# led_board_v2.net
KiCad netlist of a schematic drawn in EAGLE
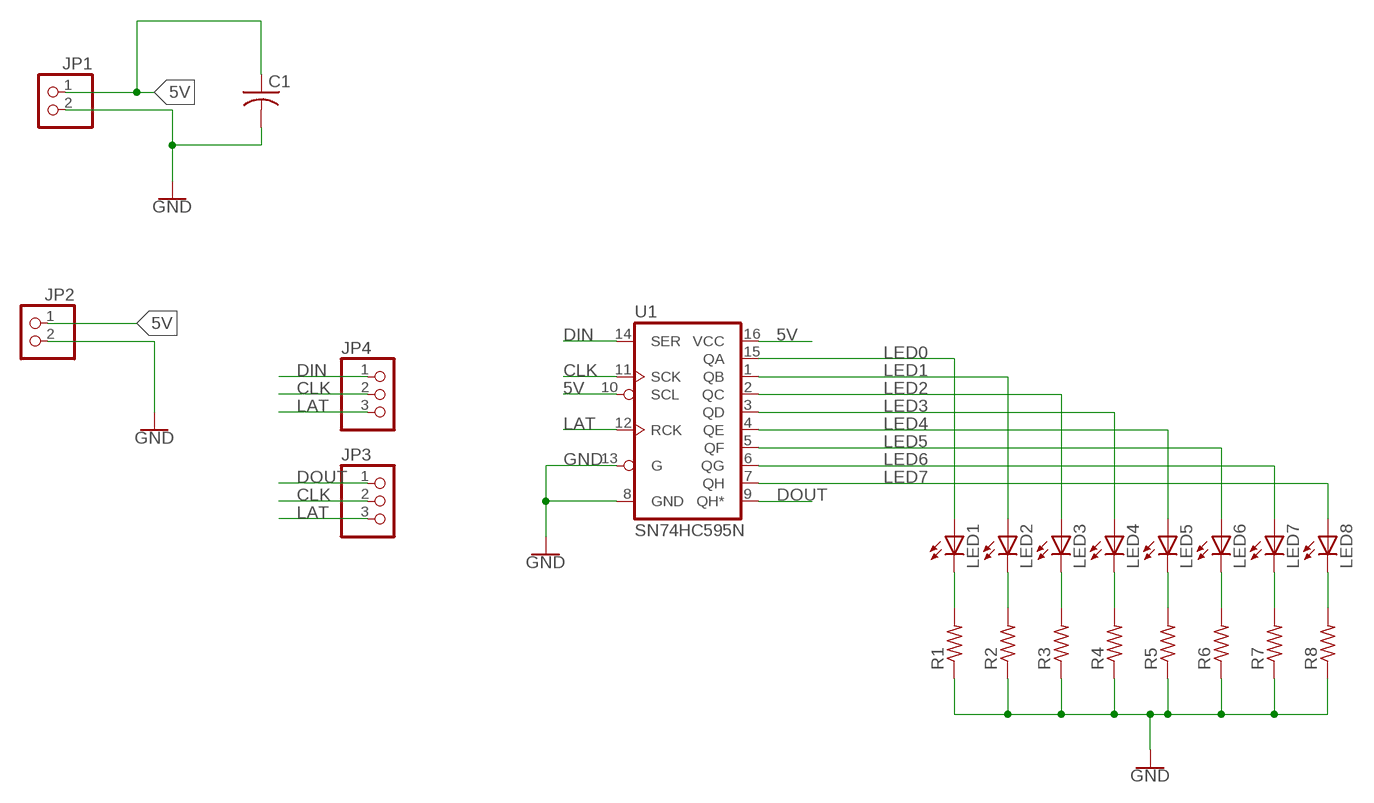
[diagram p0: schematic, sheet 1]

(export (version "E")
  (design (tool "Eeschema 10.0.6"))
  (components
    (comp (ref "C1")
      (value "C-US025-030X050")
      (footprint "eagle-import:C025-030X050")
      (libsource (lib "eagle-import") (part "C-US025-030X050"))
    )
    (comp (ref "JP1")
      (value "PINHD-1X2")
      (footprint "eagle-import:1X02")
      (libsource (lib "eagle-import") (part "PINHD-1X2"))
    )
    (comp (ref "JP2")
      (value "PINHD-1X2")
      (footprint "eagle-import:1X02")
      (libsource (lib "eagle-import") (part "PINHD-1X2"))
    )
    (comp (ref "JP3")
      (value "PINHD-1X3")
      (footprint "eagle-import:1X03")
      (libsource (lib "eagle-import") (part "PINHD-1X3"))
    )
    (comp (ref "JP4")
      (value "PINHD-1X3")
      (footprint "eagle-import:1X03")
      (libsource (lib "eagle-import") (part "PINHD-1X3"))
    )
    (comp (ref "LED1")
      (value "LED3MM")
      (footprint "eagle-import:LED3MM")
      (libsource (lib "eagle-import") (part "LED3MM"))
    )
    (comp (ref "LED2")
      (value "LED3MM")
      (footprint "eagle-import:LED3MM")
      (libsource (lib "eagle-import") (part "LED3MM"))
    )
    (comp (ref "LED3")
      (value "LED3MM")
      (footprint "eagle-import:LED3MM")
      (libsource (lib "eagle-import") (part "LED3MM"))
    )
    (comp (ref "LED4")
      (value "LED3MM")
      (footprint "eagle-import:LED3MM")
      (libsource (lib "eagle-import") (part "LED3MM"))
    )
    (comp (ref "LED5")
      (value "LED3MM")
      (footprint "eagle-import:LED3MM")
      (libsource (lib "eagle-import") (part "LED3MM"))
    )
    (comp (ref "LED6")
      (value "LED3MM")
      (footprint "eagle-import:LED3MM")
      (libsource (lib "eagle-import") (part "LED3MM"))
    )
    (comp (ref "LED7")
      (value "LED3MM")
      (footprint "eagle-import:LED3MM")
      (libsource (lib "eagle-import") (part "LED3MM"))
    )
    (comp (ref "LED8")
      (value "LED3MM")
      (footprint "eagle-import:LED3MM")
      (libsource (lib "eagle-import") (part "LED3MM"))
    )
    (comp (ref "R1")
      (value "R-US_0207/7")
      (footprint "eagle-import:0207_7")
      (libsource (lib "eagle-import") (part "R-US_0207/7"))
    )
    (comp (ref "R2")
      (value "R-US_0207/7")
      (footprint "eagle-import:0207_7")
      (libsource (lib "eagle-import") (part "R-US_0207/7"))
    )
    (comp (ref "R3")
      (value "R-US_0207/7")
      (footprint "eagle-import:0207_7")
      (libsource (lib "eagle-import") (part "R-US_0207/7"))
    )
    (comp (ref "R4")
      (value "R-US_0207/7")
      (footprint "eagle-import:0207_7")
      (libsource (lib "eagle-import") (part "R-US_0207/7"))
    )
    (comp (ref "R5")
      (value "R-US_0207/7")
      (footprint "eagle-import:0207_7")
      (libsource (lib "eagle-import") (part "R-US_0207/7"))
    )
    (comp (ref "R6")
      (value "R-US_0207/7")
      (footprint "eagle-import:0207_7")
      (libsource (lib "eagle-import") (part "R-US_0207/7"))
    )
    (comp (ref "R7")
      (value "R-US_0207/7")
      (footprint "eagle-import:0207_7")
      (libsource (lib "eagle-import") (part "R-US_0207/7"))
    )
    (comp (ref "R8")
      (value "R-US_0207/7")
      (footprint "eagle-import:0207_7")
      (libsource (lib "eagle-import") (part "R-US_0207/7"))
    )
    (comp (ref "U1")
      (value "SN74HC595N")
      (footprint "eagle-import:DIP16")
      (libsource (lib "eagle-import") (part "74595NHC"))
    )
  )
  (nets
    (net (code "1") (name "/CLK") (class "Default")
      (node (ref "JP3") (pin "2") (pinfunction "2_2") (pintype "passive"))
      (node (ref "JP4") (pin "2") (pinfunction "2_2") (pintype "passive"))
      (node (ref "U1") (pin "11") (pinfunction "SCK_11") (pintype "input"))
    )
    (net (code "2") (name "/DIN") (class "Default")
      (node (ref "JP4") (pin "1") (pinfunction "1_1") (pintype "passive"))
      (node (ref "U1") (pin "14") (pinfunction "SER_14") (pintype "input"))
    )
    (net (code "3") (name "/DOUT") (class "Default")
      (node (ref "JP3") (pin "1") (pinfunction "1_1") (pintype "passive"))
      (node (ref "U1") (pin "9") (pinfunction "QH*_9") (pintype "tri_state"))
    )
    (net (code "4") (name "/LAT") (class "Default")
      (node (ref "JP3") (pin "3") (pinfunction "3_3") (pintype "passive"))
      (node (ref "JP4") (pin "3") (pinfunction "3_3") (pintype "passive"))
      (node (ref "U1") (pin "12") (pinfunction "RCK_12") (pintype "input"))
    )
    (net (code "5") (name "/LED0") (class "Default")
      (node (ref "LED1") (pin "A") (pinfunction "A_A") (pintype "passive"))
      (node (ref "U1") (pin "15") (pinfunction "QA_15") (pintype "tri_state"))
    )
    (net (code "6") (name "/LED1") (class "Default")
      (node (ref "LED2") (pin "A") (pinfunction "A_A") (pintype "passive"))
      (node (ref "U1") (pin "1") (pinfunction "QB_1") (pintype "tri_state"))
    )
    (net (code "7") (name "/LED2") (class "Default")
      (node (ref "LED3") (pin "A") (pinfunction "A_A") (pintype "passive"))
      (node (ref "U1") (pin "2") (pinfunction "QC_2") (pintype "tri_state"))
    )
    (net (code "8") (name "/LED3") (class "Default")
      (node (ref "LED4") (pin "A") (pinfunction "A_A") (pintype "passive"))
      (node (ref "U1") (pin "3") (pinfunction "QD_3") (pintype "tri_state"))
    )
    (net (code "9") (name "/LED4") (class "Default")
      (node (ref "LED5") (pin "A") (pinfunction "A_A") (pintype "passive"))
      (node (ref "U1") (pin "4") (pinfunction "QE_4") (pintype "tri_state"))
    )
    (net (code "10") (name "/LED5") (class "Default")
      (node (ref "LED6") (pin "A") (pinfunction "A_A") (pintype "passive"))
      (node (ref "U1") (pin "5") (pinfunction "QF_5") (pintype "tri_state"))
    )
    (net (code "11") (name "/LED6") (class "Default")
      (node (ref "LED7") (pin "A") (pinfunction "A_A") (pintype "passive"))
      (node (ref "U1") (pin "6") (pinfunction "QG_6") (pintype "tri_state"))
    )
    (net (code "12") (name "/LED7") (class "Default")
      (node (ref "LED8") (pin "A") (pinfunction "A_A") (pintype "passive"))
      (node (ref "U1") (pin "7") (pinfunction "QH_7") (pintype "tri_state"))
    )
    (net (code "13") (name "5V") (class "Default")
      (node (ref "C1") (pin "1") (pinfunction "1_1") (pintype "passive"))
      (node (ref "JP1") (pin "1") (pinfunction "1_1") (pintype "passive"))
      (node (ref "JP2") (pin "1") (pinfunction "1_1") (pintype "passive"))
      (node (ref "U1") (pin "10") (pinfunction "SCL_10") (pintype "input"))
      (node (ref "U1") (pin "16") (pinfunction "VCC_16") (pintype "power_in"))
    )
    (net (code "14") (name "GND") (class "Default")
      (node (ref "C1") (pin "2") (pinfunction "2_2") (pintype "passive"))
      (node (ref "JP1") (pin "2") (pinfunction "2_2") (pintype "passive"))
      (node (ref "JP2") (pin "2") (pinfunction "2_2") (pintype "passive"))
      (node (ref "R1") (pin "1") (pinfunction "1_1") (pintype "passive"))
      (node (ref "R2") (pin "1") (pinfunction "1_1") (pintype "passive"))
      (node (ref "R3") (pin "1") (pinfunction "1_1") (pintype "passive"))
      (node (ref "R4") (pin "1") (pinfunction "1_1") (pintype "passive"))
      (node (ref "R5") (pin "1") (pinfunction "1_1") (pintype "passive"))
      (node (ref "R6") (pin "1") (pinfunction "1_1") (pintype "passive"))
      (node (ref "R7") (pin "1") (pinfunction "1_1") (pintype "passive"))
      (node (ref "R8") (pin "1") (pinfunction "1_1") (pintype "passive"))
      (node (ref "U1") (pin "13") (pinfunction "G_13") (pintype "input"))
      (node (ref "U1") (pin "8") (pinfunction "GND_8") (pintype "power_in"))
    )
    (net (code "15") (name "Net-(LED1-C)") (class "Default")
      (node (ref "LED1") (pin "K") (pinfunction "C_K") (pintype "passive"))
      (node (ref "R1") (pin "2") (pinfunction "2_2") (pintype "passive"))
    )
    (net (code "16") (name "Net-(LED2-C)") (class "Default")
      (node (ref "LED2") (pin "K") (pinfunction "C_K") (pintype "passive"))
      (node (ref "R2") (pin "2") (pinfunction "2_2") (pintype "passive"))
    )
    (net (code "17") (name "Net-(LED3-C)") (class "Default")
      (node (ref "LED3") (pin "K") (pinfunction "C_K") (pintype "passive"))
      (node (ref "R3") (pin "2") (pinfunction "2_2") (pintype "passive"))
    )
    (net (code "18") (name "Net-(LED4-C)") (class "Default")
      (node (ref "LED4") (pin "K") (pinfunction "C_K") (pintype "passive"))
      (node (ref "R4") (pin "2") (pinfunction "2_2") (pintype "passive"))
    )
    (net (code "19") (name "Net-(LED5-C)") (class "Default")
      (node (ref "LED5") (pin "K") (pinfunction "C_K") (pintype "passive"))
      (node (ref "R5") (pin "2") (pinfunction "2_2") (pintype "passive"))
    )
    (net (code "20") (name "Net-(LED6-C)") (class "Default")
      (node (ref "LED6") (pin "K") (pinfunction "C_K") (pintype "passive"))
      (node (ref "R6") (pin "2") (pinfunction "2_2") (pintype "passive"))
    )
    (net (code "21") (name "Net-(LED7-C)") (class "Default")
      (node (ref "LED7") (pin "K") (pinfunction "C_K") (pintype "passive"))
      (node (ref "R7") (pin "2") (pinfunction "2_2") (pintype "passive"))
    )
    (net (code "22") (name "Net-(LED8-C)") (class "Default")
      (node (ref "LED8") (pin "K") (pinfunction "C_K") (pintype "passive"))
      (node (ref "R8") (pin "2") (pinfunction "2_2") (pintype "passive"))
    )
  )
)
